# MotorControllerV2.net
KiCad netlist of a schematic drawn in EAGLE
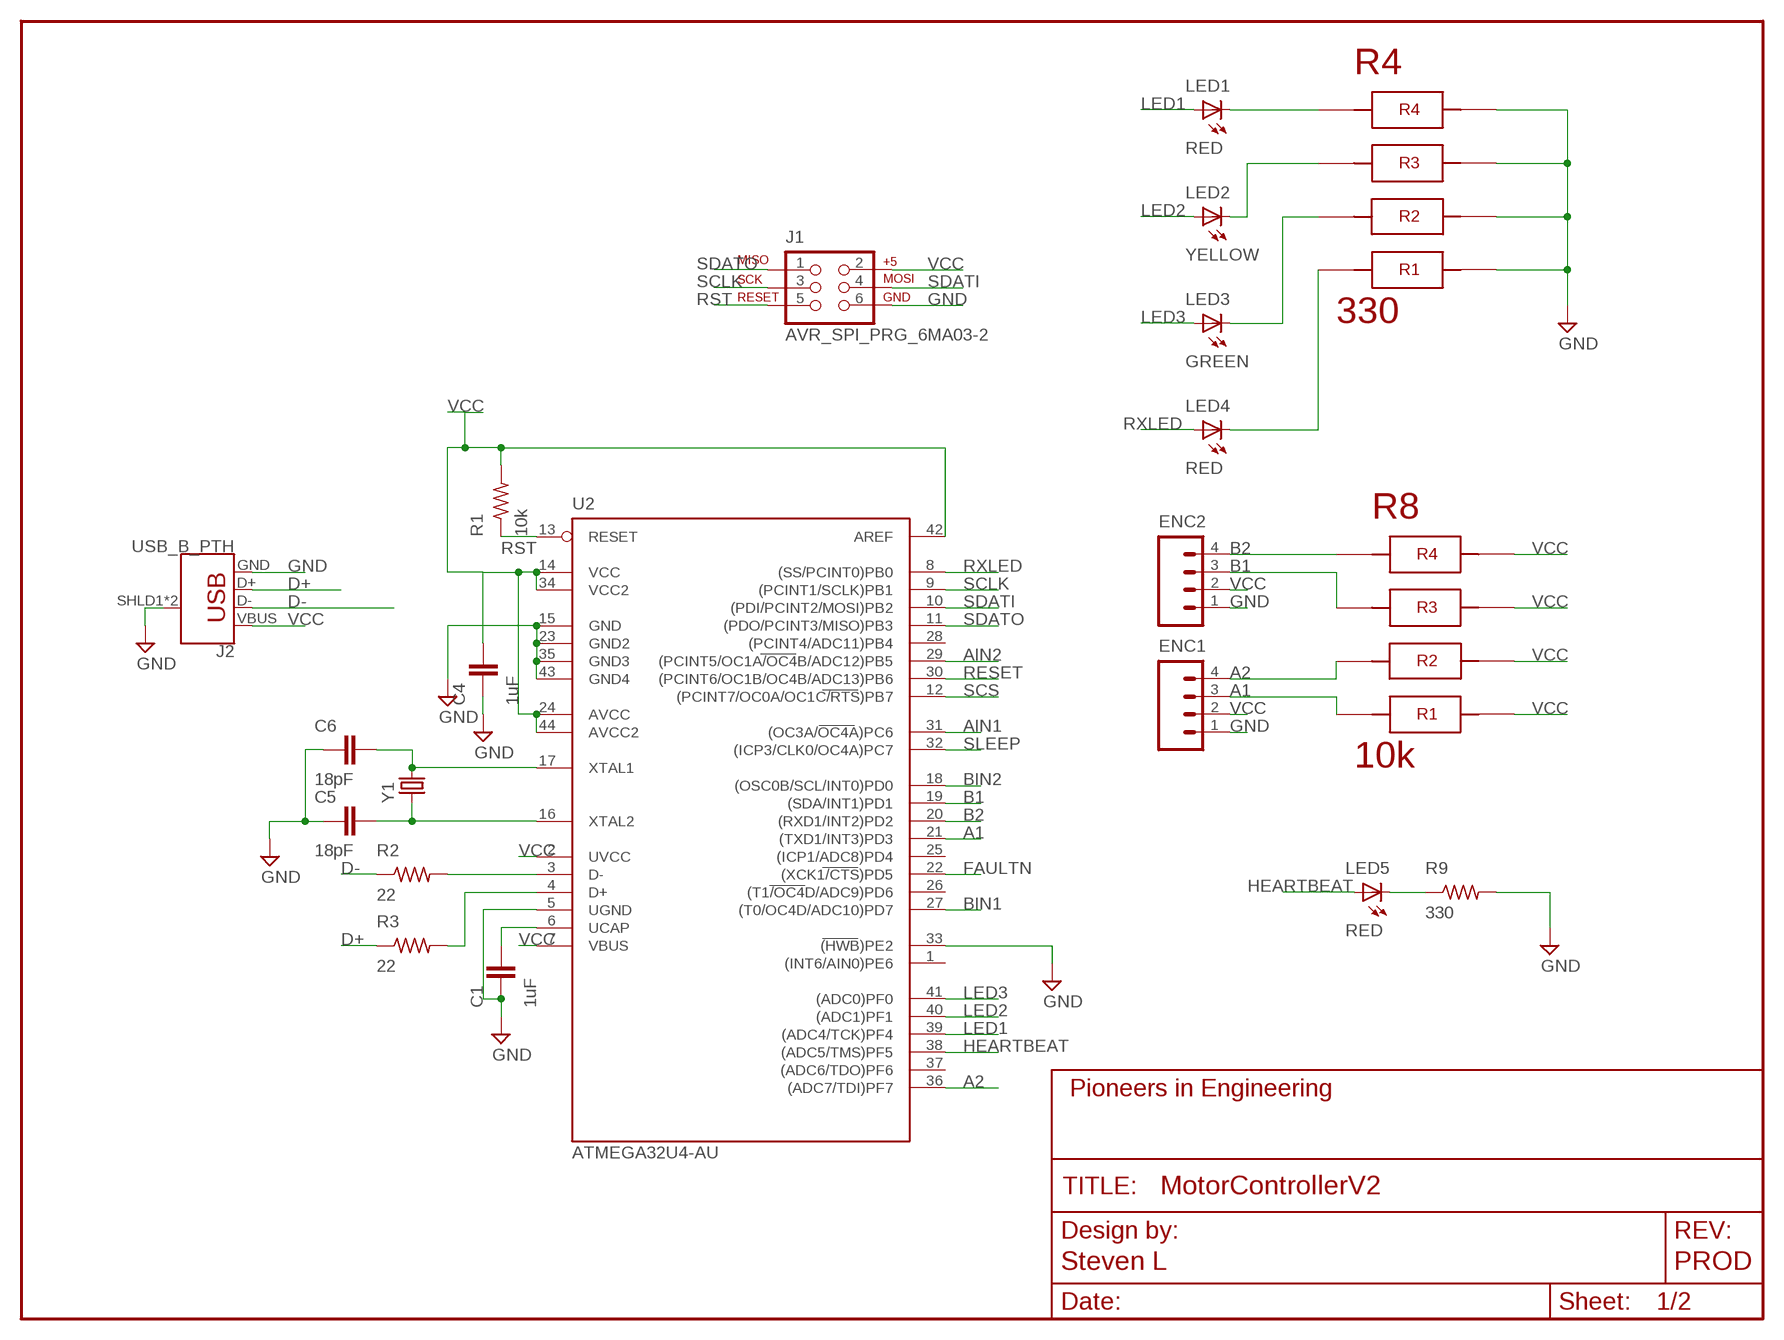
[diagram p0: schematic, sheet 1]
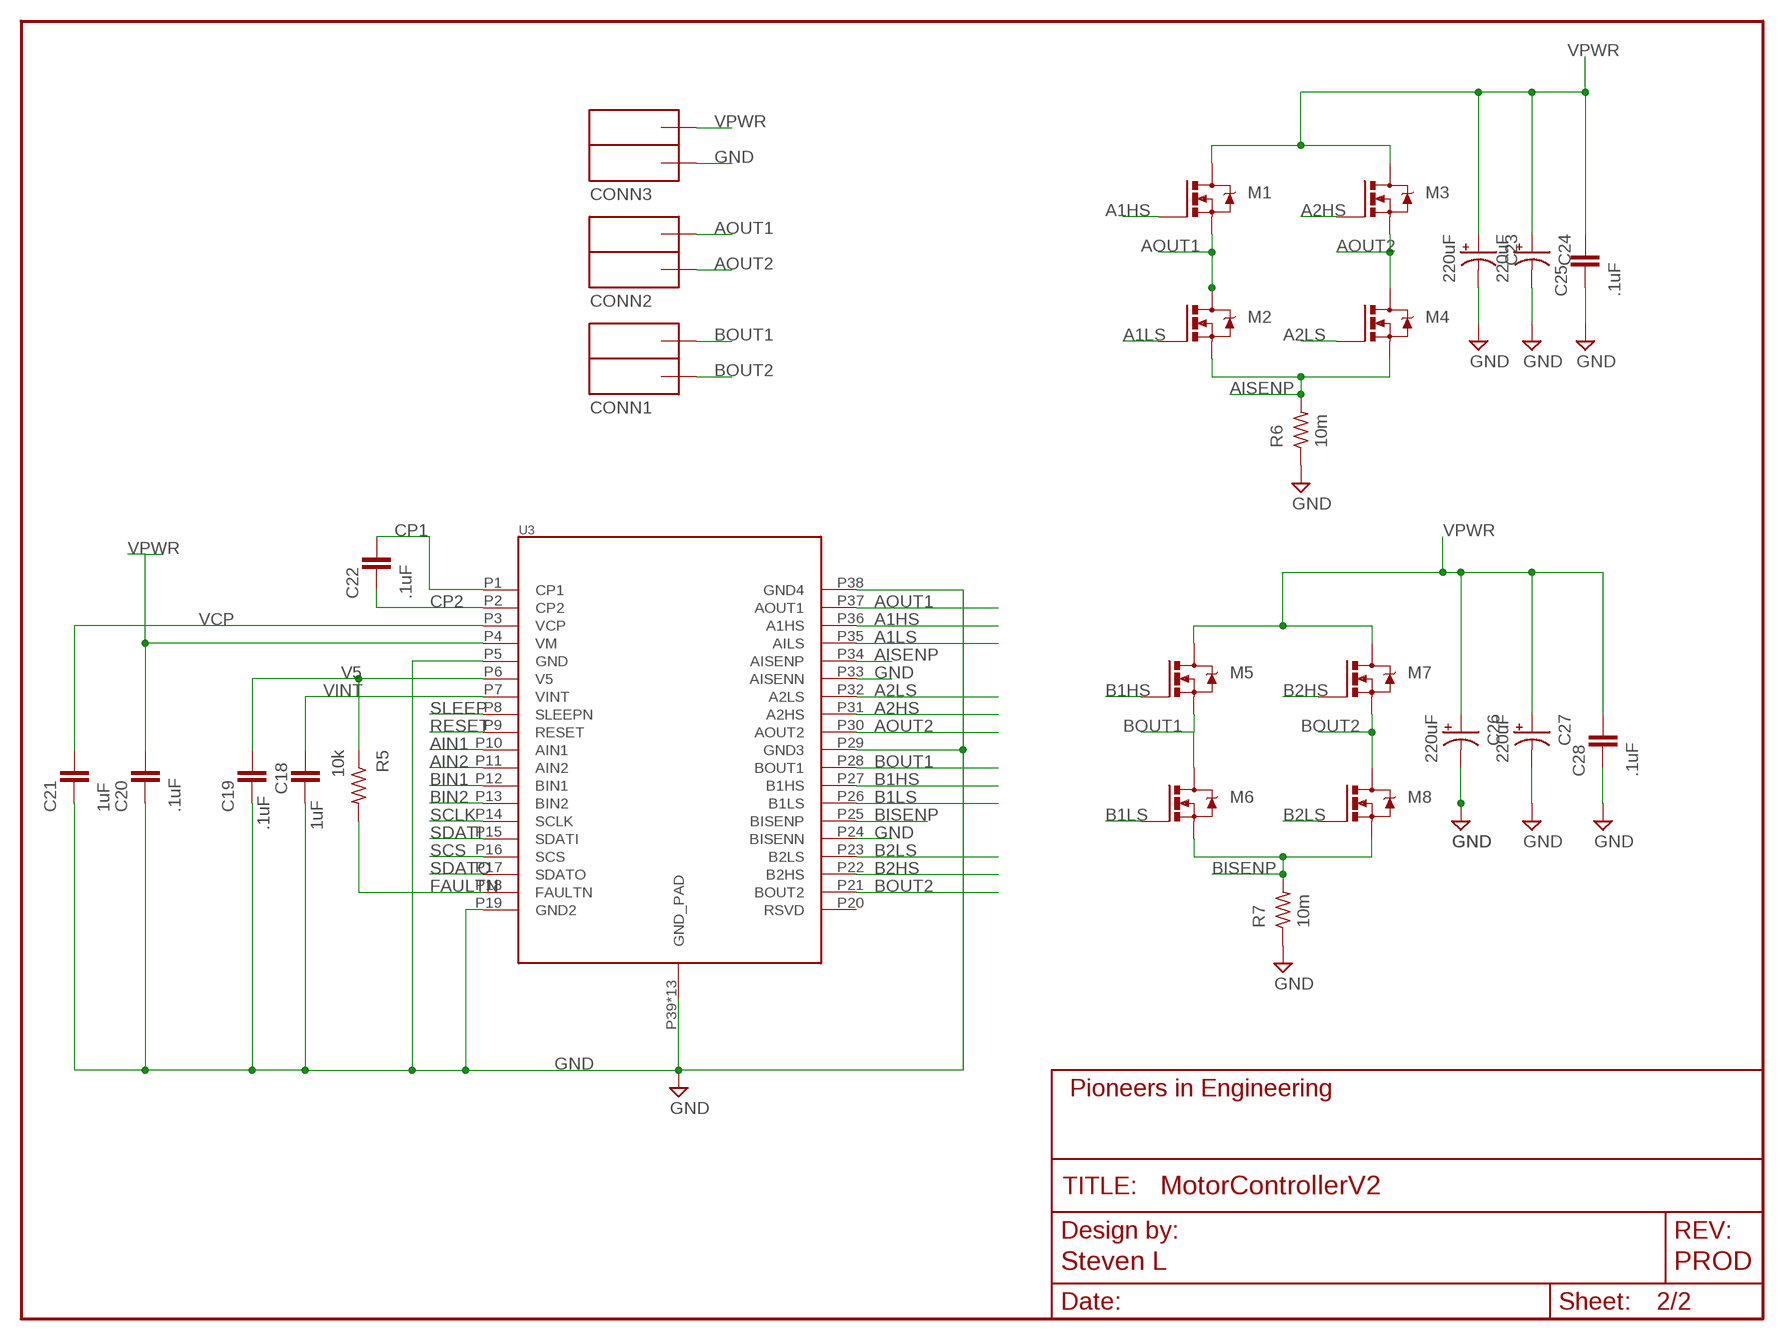
[diagram p1: schematic, sheet 2]

(export (version "E")
  (design (tool "Eeschema 10.0.6"))
  (components
    (comp (ref "C1")
      (value "1uF")
      (footprint "eagle-import:0603-CAP")
      (libsource (lib "eagle-import") (part "CAP0603-CAP"))
    )
    (comp (ref "C4")
      (value "1uF")
      (footprint "eagle-import:0603-CAP")
      (libsource (lib "eagle-import") (part "CAP0603-CAP"))
    )
    (comp (ref "C5")
      (value "18pF")
      (footprint "eagle-import:0603-CAP")
      (libsource (lib "eagle-import") (part "CAP0603-CAP"))
    )
    (comp (ref "C6")
      (value "18pF")
      (footprint "eagle-import:0603-CAP")
      (libsource (lib "eagle-import") (part "CAP0603-CAP"))
    )
    (comp (ref "ENC1")
      (value "M041X04-MTA")
      (footprint "eagle-import:1X04-MTA")
      (libsource (lib "eagle-import") (part "M041X04-MTA"))
    )
    (comp (ref "ENC2")
      (value "M041X04-MTA")
      (footprint "eagle-import:1X04-MTA")
      (libsource (lib "eagle-import") (part "M041X04-MTA"))
    )
    (comp (ref "J1")
      (value "AVR_SPI_PRG_6MA03-2")
      (footprint "eagle-import:MA03-2")
      (libsource (lib "eagle-import") (part "AVR_SPI_PRG_6MA03-2"))
    )
    (comp (ref "J2")
      (value "USB_B_PTH")
      (footprint "eagle-import:USB-B-PTH")
      (libsource (lib "eagle-import") (part "USB_B_PTH"))
    )
    (comp (ref "LED1")
      (value "RED")
      (footprint "eagle-import:LED-1206")
      (libsource (lib "eagle-import") (part "LED1206"))
    )
    (comp (ref "LED2")
      (value "YELLOW")
      (footprint "eagle-import:LED-1206")
      (libsource (lib "eagle-import") (part "LED1206"))
    )
    (comp (ref "LED3")
      (value "GREEN")
      (footprint "eagle-import:LED-1206")
      (libsource (lib "eagle-import") (part "LED1206"))
    )
    (comp (ref "LED4")
      (value "RED")
      (footprint "eagle-import:LED-1206")
      (libsource (lib "eagle-import") (part "LED1206"))
    )
    (comp (ref "LED5")
      (value "RED")
      (footprint "eagle-import:LED-1206")
      (libsource (lib "eagle-import") (part "LED1206"))
    )
    (comp (ref "R1")
      (value "10k")
      (footprint "eagle-import:R0603")
      (fields (field (name "MANUFACTURER") "Rohm Semiconductor"))
      (libsource (lib "eagle-import") (part "R-US_R0603"))
    )
    (comp (ref "R2")
      (value "22")
      (footprint "eagle-import:R0603")
      (fields (field (name "MANUFACTURER") "Rohm Semiconductor"))
      (libsource (lib "eagle-import") (part "R-US_R0603"))
    )
    (comp (ref "R3")
      (value "22")
      (footprint "eagle-import:R0603")
      (fields (field (name "MANUFACTURER") "Rohm Semiconductor"))
      (libsource (lib "eagle-import") (part "R-US_R0603"))
    )
    (comp (ref "R4")
      (value "330")
      (footprint "eagle-import:4X-0603")
      (libsource (lib "eagle-import") (part "4X-0603"))
    )
    (comp (ref "R8")
      (value "10k")
      (footprint "eagle-import:4X-0603")
      (libsource (lib "eagle-import") (part "4X-0603"))
    )
    (comp (ref "R9")
      (value "330")
      (footprint "eagle-import:R0603")
      (fields (field (name "MANUFACTURER") "Rohm Semiconductor"))
      (libsource (lib "eagle-import") (part "R-US_R0603"))
    )
    (comp (ref "U2")
      (value "ATMEGA32U4-AU")
      (footprint "eagle-import:TQFP44")
      (libsource (lib "eagle-import") (part "ATMEGA32U4-AU"))
    )
    (comp (ref "Y1")
      (value "CRYSTAL10.5X4.8")
      (footprint "eagle-import:CRYSTAL-SMD-10.5X4.8-2PIN")
      (libsource (lib "eagle-import") (part "CRYSTAL10.5X4.8"))
    )
    (comp (ref "C18")
      (value "1uF")
      (footprint "eagle-import:0603-CAP")
      (libsource (lib "eagle-import") (part "CAP0603-CAP"))
    )
    (comp (ref "C19")
      (value ".1uF")
      (footprint "eagle-import:0603-CAP")
      (libsource (lib "eagle-import") (part "CAP0603-CAP"))
    )
    (comp (ref "C20")
      (value ".1uF")
      (footprint "eagle-import:0603-CAP")
      (libsource (lib "eagle-import") (part "CAP0603-CAP"))
    )
    (comp (ref "C21")
      (value "1uF")
      (footprint "eagle-import:0603-CAP")
      (libsource (lib "eagle-import") (part "CAP0603-CAP"))
    )
    (comp (ref "C22")
      (value ".1uF")
      (footprint "eagle-import:0603-CAP")
      (libsource (lib "eagle-import") (part "CAP0603-CAP"))
    )
    (comp (ref "C23")
      (value "220uF")
      (footprint "eagle-import:NIPPON_F80")
      (libsource (lib "eagle-import") (part "CAP_POLF80"))
    )
    (comp (ref "C24")
      (value "220uF")
      (footprint "eagle-import:NIPPON_F80")
      (libsource (lib "eagle-import") (part "CAP_POLF80"))
    )
    (comp (ref "C25")
      (value ".1uF")
      (footprint "eagle-import:0603-CAP")
      (libsource (lib "eagle-import") (part "CAP0603-CAP"))
    )
    (comp (ref "C26")
      (value "220uF")
      (footprint "eagle-import:NIPPON_F80")
      (libsource (lib "eagle-import") (part "CAP_POLF80"))
    )
    (comp (ref "C27")
      (value "220uF")
      (footprint "eagle-import:NIPPON_F80")
      (libsource (lib "eagle-import") (part "CAP_POLF80"))
    )
    (comp (ref "C28")
      (value ".1uF")
      (footprint "eagle-import:0603-CAP")
      (libsource (lib "eagle-import") (part "CAP0603-CAP"))
    )
    (comp (ref "CONN1")
      (value "ANDERSONVERTICAL")
      (footprint "eagle-import:ANDERSON_VERTICAL")
      (libsource (lib "eagle-import") (part "ANDERSONVERTICAL"))
    )
    (comp (ref "CONN2")
      (value "ANDERSONVERTICAL")
      (footprint "eagle-import:ANDERSON_VERTICAL")
      (libsource (lib "eagle-import") (part "ANDERSONVERTICAL"))
    )
    (comp (ref "CONN3")
      (value "ANDERSONVERTICAL")
      (footprint "eagle-import:ANDERSON_VERTICAL")
      (libsource (lib "eagle-import") (part "ANDERSONVERTICAL"))
    )
    (comp (ref "M1")
      (value "NMOS_CSD17579Q3A")
      (footprint "eagle-import:DNH0008A")
      (fields (field (name "PART_NO") "CSD17579Q3A"))
      (libsource (lib "eagle-import") (part "NMOS_CSD17579Q3A"))
    )
    (comp (ref "M2")
      (value "NMOS_CSD17579Q3A")
      (footprint "eagle-import:DNH0008A")
      (fields (field (name "PART_NO") "CSD17579Q3A"))
      (libsource (lib "eagle-import") (part "NMOS_CSD17579Q3A"))
    )
    (comp (ref "M3")
      (value "NMOS_CSD17579Q3A")
      (footprint "eagle-import:DNH0008A")
      (fields (field (name "PART_NO") "CSD17579Q3A"))
      (libsource (lib "eagle-import") (part "NMOS_CSD17579Q3A"))
    )
    (comp (ref "M4")
      (value "NMOS_CSD17579Q3A")
      (footprint "eagle-import:DNH0008A")
      (fields (field (name "PART_NO") "CSD17579Q3A"))
      (libsource (lib "eagle-import") (part "NMOS_CSD17579Q3A"))
    )
    (comp (ref "M5")
      (value "NMOS_CSD17579Q3A")
      (footprint "eagle-import:DNH0008A")
      (fields (field (name "PART_NO") "CSD17579Q3A"))
      (libsource (lib "eagle-import") (part "NMOS_CSD17579Q3A"))
    )
    (comp (ref "M6")
      (value "NMOS_CSD17579Q3A")
      (footprint "eagle-import:DNH0008A")
      (fields (field (name "PART_NO") "CSD17579Q3A"))
      (libsource (lib "eagle-import") (part "NMOS_CSD17579Q3A"))
    )
    (comp (ref "M7")
      (value "NMOS_CSD17579Q3A")
      (footprint "eagle-import:DNH0008A")
      (fields (field (name "PART_NO") "CSD17579Q3A"))
      (libsource (lib "eagle-import") (part "NMOS_CSD17579Q3A"))
    )
    (comp (ref "M8")
      (value "NMOS_CSD17579Q3A")
      (footprint "eagle-import:DNH0008A")
      (fields (field (name "PART_NO") "CSD17579Q3A"))
      (libsource (lib "eagle-import") (part "NMOS_CSD17579Q3A"))
    )
    (comp (ref "R5")
      (value "10k")
      (footprint "eagle-import:R0603")
      (fields (field (name "MANUFACTURER") "Rohm Semiconductor"))
      (libsource (lib "eagle-import") (part "R-US_R0603"))
    )
    (comp (ref "R6")
      (value "10m")
      (footprint "eagle-import:R2512")
      (libsource (lib "eagle-import") (part "R-US_R2512"))
    )
    (comp (ref "R7")
      (value "10m")
      (footprint "eagle-import:R2512")
      (libsource (lib "eagle-import") (part "R-US_R2512"))
    )
    (comp (ref "U3")
      (value "DRV8704")
      (footprint "eagle-import:HTSSOP(38)")
      (libsource (lib "eagle-import") (part "DRV8704"))
    )
  )
  (nets
    (net (code "1") (name "A1") (class "Default")
      (node (ref "ENC1") (pin "3") (pinfunction "3_3") (pintype "passive"))
      (node (ref "R8") (pin "8") (pinfunction "8_8") (pintype "bidirectional"))
      (node (ref "U2") (pin "21") (pinfunction "(TXD1/INT3)PD3_21") (pintype "bidirectional"))
    )
    (net (code "2") (name "A1HS") (class "Default")
      (node (ref "M1") (pin "4") (pinfunction "G_4") (pintype "passive"))
      (node (ref "U3") (pin "P36") (pinfunction "A1HS_P36") (pintype "bidirectional"))
    )
    (net (code "3") (name "A1LS") (class "Default")
      (node (ref "M2") (pin "4") (pinfunction "G_4") (pintype "passive"))
      (node (ref "U3") (pin "P35") (pinfunction "AILS_P35") (pintype "bidirectional"))
    )
    (net (code "4") (name "A2") (class "Default")
      (node (ref "ENC1") (pin "4") (pinfunction "4_4") (pintype "passive"))
      (node (ref "R8") (pin "7") (pinfunction "7_7") (pintype "bidirectional"))
      (node (ref "U2") (pin "36") (pinfunction "(ADC7/TDI)PF7_36") (pintype "bidirectional"))
    )
    (net (code "5") (name "A2HS") (class "Default")
      (node (ref "M3") (pin "4") (pinfunction "G_4") (pintype "passive"))
      (node (ref "U3") (pin "P31") (pinfunction "A2HS_P31") (pintype "bidirectional"))
    )
    (net (code "6") (name "A2LS") (class "Default")
      (node (ref "M4") (pin "4") (pinfunction "G_4") (pintype "passive"))
      (node (ref "U3") (pin "P32") (pinfunction "A2LS_P32") (pintype "bidirectional"))
    )
    (net (code "7") (name "AIN1") (class "Default")
      (node (ref "U2") (pin "31") (pinfunction "(OC3A/OC4A)PC6_31") (pintype "bidirectional"))
      (node (ref "U3") (pin "P10") (pinfunction "AIN1_P10") (pintype "bidirectional"))
    )
    (net (code "8") (name "AIN2") (class "Default")
      (node (ref "U2") (pin "29") (pinfunction "(PCINT5/OC1A/OC4B/ADC12)PB5_29") (pintype "bidirectional"))
      (node (ref "U3") (pin "P11") (pinfunction "AIN2_P11") (pintype "bidirectional"))
    )
    (net (code "9") (name "AISENP") (class "Default")
      (node (ref "M2") (pin "1") (pinfunction "S_1") (pintype "passive"))
      (node (ref "M2") (pin "2") (pinfunction "S_2") (pintype "passive"))
      (node (ref "M2") (pin "3") (pinfunction "S_3") (pintype "passive"))
      (node (ref "M4") (pin "1") (pinfunction "S_1") (pintype "passive"))
      (node (ref "M4") (pin "2") (pinfunction "S_2") (pintype "passive"))
      (node (ref "M4") (pin "3") (pinfunction "S_3") (pintype "passive"))
      (node (ref "R6") (pin "2") (pinfunction "2_2") (pintype "passive"))
      (node (ref "U3") (pin "P34") (pinfunction "AISENP_P34") (pintype "bidirectional"))
    )
    (net (code "10") (name "AOUT1") (class "Default")
      (node (ref "CONN2") (pin "PIN1") (pinfunction "OUTB_PIN1") (pintype "bidirectional"))
      (node (ref "M1") (pin "1") (pinfunction "S_1") (pintype "passive"))
      (node (ref "M1") (pin "2") (pinfunction "S_2") (pintype "passive"))
      (node (ref "M1") (pin "3") (pinfunction "S_3") (pintype "passive"))
      (node (ref "M2") (pin "5") (pinfunction "D_5") (pintype "passive"))
      (node (ref "M2") (pin "6") (pinfunction "D_6") (pintype "passive"))
      (node (ref "M2") (pin "7") (pinfunction "D_7") (pintype "passive"))
      (node (ref "M2") (pin "8") (pinfunction "D_8") (pintype "passive"))
      (node (ref "M2") (pin "9") (pinfunction "D_9") (pintype "passive"))
      (node (ref "U3") (pin "P37") (pinfunction "AOUT1_P37") (pintype "bidirectional"))
    )
    (net (code "11") (name "AOUT2") (class "Default")
      (node (ref "CONN2") (pin "PIN2") (pinfunction "OUTA_PIN2") (pintype "bidirectional"))
      (node (ref "M3") (pin "1") (pinfunction "S_1") (pintype "passive"))
      (node (ref "M3") (pin "2") (pinfunction "S_2") (pintype "passive"))
      (node (ref "M3") (pin "3") (pinfunction "S_3") (pintype "passive"))
      (node (ref "M4") (pin "5") (pinfunction "D_5") (pintype "passive"))
      (node (ref "M4") (pin "6") (pinfunction "D_6") (pintype "passive"))
      (node (ref "M4") (pin "7") (pinfunction "D_7") (pintype "passive"))
      (node (ref "M4") (pin "8") (pinfunction "D_8") (pintype "passive"))
      (node (ref "M4") (pin "9") (pinfunction "D_9") (pintype "passive"))
      (node (ref "U3") (pin "P30") (pinfunction "AOUT2_P30") (pintype "bidirectional"))
    )
    (net (code "12") (name "B1") (class "Default")
      (node (ref "ENC2") (pin "3") (pinfunction "3_3") (pintype "passive"))
      (node (ref "R8") (pin "6") (pinfunction "6_6") (pintype "bidirectional"))
      (node (ref "U2") (pin "19") (pinfunction "(SDA/INT1)PD1_19") (pintype "bidirectional"))
    )
    (net (code "13") (name "B1HS") (class "Default")
      (node (ref "M5") (pin "4") (pinfunction "G_4") (pintype "passive"))
      (node (ref "U3") (pin "P27") (pinfunction "B1HS_P27") (pintype "bidirectional"))
    )
    (net (code "14") (name "B1LS") (class "Default")
      (node (ref "M6") (pin "4") (pinfunction "G_4") (pintype "passive"))
      (node (ref "U3") (pin "P26") (pinfunction "B1LS_P26") (pintype "bidirectional"))
    )
    (net (code "15") (name "B2") (class "Default")
      (node (ref "ENC2") (pin "4") (pinfunction "4_4") (pintype "passive"))
      (node (ref "R8") (pin "5") (pinfunction "5_5") (pintype "bidirectional"))
      (node (ref "U2") (pin "20") (pinfunction "(RXD1/INT2)PD2_20") (pintype "bidirectional"))
    )
    (net (code "16") (name "B2HS") (class "Default")
      (node (ref "M7") (pin "4") (pinfunction "G_4") (pintype "passive"))
      (node (ref "U3") (pin "P22") (pinfunction "B2HS_P22") (pintype "bidirectional"))
    )
    (net (code "17") (name "B2LS") (class "Default")
      (node (ref "M8") (pin "4") (pinfunction "G_4") (pintype "passive"))
      (node (ref "U3") (pin "P23") (pinfunction "B2LS_P23") (pintype "bidirectional"))
    )
    (net (code "18") (name "BIN1") (class "Default")
      (node (ref "U2") (pin "27") (pinfunction "(T0/OC4D/ADC10)PD7_27") (pintype "bidirectional"))
      (node (ref "U3") (pin "P12") (pinfunction "BIN1_P12") (pintype "bidirectional"))
    )
    (net (code "19") (name "BIN2") (class "Default")
      (node (ref "U2") (pin "18") (pinfunction "(OSC0B/SCL/INT0)PD0_18") (pintype "bidirectional"))
      (node (ref "U3") (pin "P13") (pinfunction "BIN2_P13") (pintype "bidirectional"))
    )
    (net (code "20") (name "BISENP") (class "Default")
      (node (ref "M6") (pin "1") (pinfunction "S_1") (pintype "passive"))
      (node (ref "M6") (pin "2") (pinfunction "S_2") (pintype "passive"))
      (node (ref "M6") (pin "3") (pinfunction "S_3") (pintype "passive"))
      (node (ref "M8") (pin "1") (pinfunction "S_1") (pintype "passive"))
      (node (ref "M8") (pin "2") (pinfunction "S_2") (pintype "passive"))
      (node (ref "M8") (pin "3") (pinfunction "S_3") (pintype "passive"))
      (node (ref "R7") (pin "2") (pinfunction "2_2") (pintype "passive"))
      (node (ref "U3") (pin "P25") (pinfunction "BISENP_P25") (pintype "bidirectional"))
    )
    (net (code "21") (name "BOUT1") (class "Default")
      (node (ref "CONN1") (pin "PIN1") (pinfunction "OUTB_PIN1") (pintype "bidirectional"))
      (node (ref "M5") (pin "1") (pinfunction "S_1") (pintype "passive"))
      (node (ref "M5") (pin "2") (pinfunction "S_2") (pintype "passive"))
      (node (ref "M5") (pin "3") (pinfunction "S_3") (pintype "passive"))
      (node (ref "M6") (pin "5") (pinfunction "D_5") (pintype "passive"))
      (node (ref "M6") (pin "6") (pinfunction "D_6") (pintype "passive"))
      (node (ref "M6") (pin "7") (pinfunction "D_7") (pintype "passive"))
      (node (ref "M6") (pin "8") (pinfunction "D_8") (pintype "passive"))
      (node (ref "M6") (pin "9") (pinfunction "D_9") (pintype "passive"))
      (node (ref "U3") (pin "P28") (pinfunction "BOUT1_P28") (pintype "bidirectional"))
    )
    (net (code "22") (name "BOUT2") (class "Default")
      (node (ref "CONN1") (pin "PIN2") (pinfunction "OUTA_PIN2") (pintype "bidirectional"))
      (node (ref "M7") (pin "1") (pinfunction "S_1") (pintype "passive"))
      (node (ref "M7") (pin "2") (pinfunction "S_2") (pintype "passive"))
      (node (ref "M7") (pin "3") (pinfunction "S_3") (pintype "passive"))
      (node (ref "M8") (pin "5") (pinfunction "D_5") (pintype "passive"))
      (node (ref "M8") (pin "6") (pinfunction "D_6") (pintype "passive"))
      (node (ref "M8") (pin "7") (pinfunction "D_7") (pintype "passive"))
      (node (ref "M8") (pin "8") (pinfunction "D_8") (pintype "passive"))
      (node (ref "M8") (pin "9") (pinfunction "D_9") (pintype "passive"))
      (node (ref "U3") (pin "P21") (pinfunction "BOUT2_P21") (pintype "bidirectional"))
    )
    (net (code "23") (name "CP1") (class "Default")
      (node (ref "C22") (pin "2") (pinfunction "2_2") (pintype "passive"))
      (node (ref "U3") (pin "P1") (pinfunction "CP1_P1") (pintype "bidirectional"))
    )
    (net (code "24") (name "CP2") (class "Default")
      (node (ref "C22") (pin "1") (pinfunction "1_1") (pintype "passive"))
      (node (ref "U3") (pin "P2") (pinfunction "CP2_P2") (pintype "bidirectional"))
    )
    (net (code "25") (name "D+") (class "Default")
      (node (ref "J2") (pin "D+") (pinfunction "D+_D+") (pintype "bidirectional"))
      (node (ref "R3") (pin "1") (pinfunction "1_1") (pintype "passive"))
    )
    (net (code "26") (name "D-") (class "Default")
      (node (ref "J2") (pin "D-") (pinfunction "D-_D-") (pintype "bidirectional"))
      (node (ref "R2") (pin "1") (pinfunction "1_1") (pintype "passive"))
    )
    (net (code "27") (name "FAULTN") (class "Default")
      (node (ref "R5") (pin "2") (pinfunction "2_2") (pintype "passive"))
      (node (ref "U2") (pin "22") (pinfunction "(XCK1/CTS)PD5_22") (pintype "bidirectional"))
      (node (ref "U3") (pin "P18") (pinfunction "FAULTN_P18") (pintype "bidirectional"))
    )
    (net (code "28") (name "GND") (class "Default")
      (node (ref "C1") (pin "1") (pinfunction "1_1") (pintype "passive"))
      (node (ref "C18") (pin "1") (pinfunction "1_1") (pintype "passive"))
      (node (ref "C19") (pin "1") (pinfunction "1_1") (pintype "passive"))
      (node (ref "C20") (pin "1") (pinfunction "1_1") (pintype "passive"))
      (node (ref "C21") (pin "1") (pinfunction "1_1") (pintype "passive"))
      (node (ref "C23") (pin "-") (pinfunction "-_-") (pintype "passive"))
      (node (ref "C24") (pin "-") (pinfunction "-_-") (pintype "passive"))
      (node (ref "C25") (pin "1") (pinfunction "1_1") (pintype "passive"))
      (node (ref "C26") (pin "-") (pinfunction "-_-") (pintype "passive"))
      (node (ref "C27") (pin "-") (pinfunction "-_-") (pintype "passive"))
      (node (ref "C28") (pin "1") (pinfunction "1_1") (pintype "passive"))
      (node (ref "C4") (pin "1") (pinfunction "1_1") (pintype "passive"))
      (node (ref "C5") (pin "1") (pinfunction "1_1") (pintype "passive"))
      (node (ref "C6") (pin "1") (pinfunction "1_1") (pintype "passive"))
      (node (ref "CONN3") (pin "PIN2") (pinfunction "OUTA_PIN2") (pintype "bidirectional"))
      (node (ref "ENC1") (pin "1") (pinfunction "1_1") (pintype "passive"))
      (node (ref "ENC2") (pin "1") (pinfunction "1_1") (pintype "passive"))
      (node (ref "J1") (pin "6") (pinfunction "6_6") (pintype "passive"))
      (node (ref "J2") (pin "GND") (pinfunction "GND_GND") (pintype "power_in"))
      (node (ref "J2") (pin "SHLD1") (pinfunction "SHIELD_SHLD1") (pintype "bidirectional"))
      (node (ref "J2") (pin "SHLD2") (pinfunction "SHIELD_SHLD2") (pintype "bidirectional"))
      (node (ref "R4") (pin "1") (pinfunction "1_1") (pintype "bidirectional"))
      (node (ref "R4") (pin "2") (pinfunction "2_2") (pintype "bidirectional"))
      (node (ref "R4") (pin "3") (pinfunction "3_3") (pintype "bidirectional"))
      (node (ref "R4") (pin "4") (pinfunction "4_4") (pintype "bidirectional"))
      (node (ref "R6") (pin "1") (pinfunction "1_1") (pintype "passive"))
      (node (ref "R7") (pin "1") (pinfunction "1_1") (pintype "passive"))
      (node (ref "R9") (pin "2") (pinfunction "2_2") (pintype "passive"))
      (node (ref "U2") (pin "15") (pinfunction "GND_15") (pintype "bidirectional"))
      (node (ref "U2") (pin "23") (pinfunction "GND2_23") (pintype "bidirectional"))
      (node (ref "U2") (pin "33") (pinfunction "(HWB)PE2_33") (pintype "bidirectional"))
      (node (ref "U2") (pin "35") (pinfunction "GND3_35") (pintype "bidirectional"))
      (node (ref "U2") (pin "43") (pinfunction "GND4_43") (pintype "bidirectional"))
      (node (ref "U2") (pin "5") (pinfunction "UGND_5") (pintype "bidirectional"))
      (node (ref "U3") (pin "P19") (pinfunction "GND2_P19") (pintype "bidirectional"))
      (node (ref "U3") (pin "P24") (pinfunction "BISENN_P24") (pintype "bidirectional"))
      (node (ref "U3") (pin "P29") (pinfunction "GND3_P29") (pintype "bidirectional"))
      (node (ref "U3") (pin "P33") (pinfunction "AISENN_P33") (pintype "bidirectional"))
      (node (ref "U3") (pin "P38") (pinfunction "GND4_P38") (pintype "bidirectional"))
      (node (ref "U3") (pin "P39") (pinfunction "GND_PAD_P39") (pintype "bidirectional"))
      (node (ref "U3") (pin "P40") (pinfunction "GND_PAD_P40") (pintype "bidirectional"))
      (node (ref "U3") (pin "P41") (pinfunction "GND_PAD_P41") (pintype "bidirectional"))
      (node (ref "U3") (pin "P42") (pinfunction "GND_PAD_P42") (pintype "bidirectional"))
      (node (ref "U3") (pin "P43") (pinfunction "GND_PAD_P43") (pintype "bidirectional"))
      (node (ref "U3") (pin "P44") (pinfunction "GND_PAD_P44") (pintype "bidirectional"))
      (node (ref "U3") (pin "P45") (pinfunction "GND_PAD_P45") (pintype "bidirectional"))
      (node (ref "U3") (pin "P46") (pinfunction "GND_PAD_P46") (pintype "bidirectional"))
      (node (ref "U3") (pin "P47") (pinfunction "GND_PAD_P47") (pintype "bidirectional"))
      (node (ref "U3") (pin "P48") (pinfunction "GND_PAD_P48") (pintype "bidirectional"))
      (node (ref "U3") (pin "P49") (pinfunction "GND_PAD_P49") (pintype "bidirectional"))
      (node (ref "U3") (pin "P5") (pinfunction "GND_P5") (pintype "bidirectional"))
      (node (ref "U3") (pin "P50") (pinfunction "GND_PAD_P50") (pintype "bidirectional"))
      (node (ref "U3") (pin "P51") (pinfunction "GND_PAD_P51") (pintype "bidirectional"))
    )
    (net (code "29") (name "HEARTBEAT") (class "Default")
      (node (ref "LED5") (pin "A") (pinfunction "A_A") (pintype "passive"))
      (node (ref "U2") (pin "38") (pinfunction "(ADC5/TMS)PF5_38") (pintype "bidirectional"))
    )
    (net (code "30") (name "LED1") (class "Default")
      (node (ref "LED1") (pin "A") (pinfunction "A_A") (pintype "passive"))
      (node (ref "U2") (pin "39") (pinfunction "(ADC4/TCK)PF4_39") (pintype "bidirectional"))
    )
    (net (code "31") (name "LED2") (class "Default")
      (node (ref "LED2") (pin "A") (pinfunction "A_A") (pintype "passive"))
      (node (ref "U2") (pin "40") (pinfunction "(ADC1)PF1_40") (pintype "bidirectional"))
    )
    (net (code "32") (name "LED3") (class "Default")
      (node (ref "LED3") (pin "A") (pinfunction "A_A") (pintype "passive"))
      (node (ref "U2") (pin "41") (pinfunction "(ADC0)PF0_41") (pintype "bidirectional"))
    )
    (net (code "33") (name "Net-(LED1-PadC)") (class "Default")
      (node (ref "LED1") (pin "C") (pinfunction "C_C") (pintype "passive"))
      (node (ref "R4") (pin "5") (pinfunction "5_5") (pintype "bidirectional"))
    )
    (net (code "34") (name "Net-(LED2-PadC)") (class "Default")
      (node (ref "LED2") (pin "C") (pinfunction "C_C") (pintype "passive"))
      (node (ref "R4") (pin "6") (pinfunction "6_6") (pintype "bidirectional"))
    )
    (net (code "35") (name "Net-(LED3-PadC)") (class "Default")
      (node (ref "LED3") (pin "C") (pinfunction "C_C") (pintype "passive"))
      (node (ref "R4") (pin "7") (pinfunction "7_7") (pintype "bidirectional"))
    )
    (net (code "36") (name "Net-(LED4-PadC)") (class "Default")
      (node (ref "LED4") (pin "C") (pinfunction "C_C") (pintype "passive"))
      (node (ref "R4") (pin "8") (pinfunction "8_8") (pintype "bidirectional"))
    )
    (net (code "37") (name "Net-(LED5-PadC)") (class "Default")
      (node (ref "LED5") (pin "C") (pinfunction "C_C") (pintype "passive"))
      (node (ref "R9") (pin "1") (pinfunction "1_1") (pintype "passive"))
    )
    (net (code "38") (name "Net-(U2-D+)") (class "Default")
      (node (ref "R3") (pin "2") (pinfunction "2_2") (pintype "passive"))
      (node (ref "U2") (pin "4") (pinfunction "D+_4") (pintype "bidirectional"))
    )
    (net (code "39") (name "Net-(U2-D-)") (class "Default")
      (node (ref "R2") (pin "2") (pinfunction "2_2") (pintype "passive"))
      (node (ref "U2") (pin "3") (pinfunction "D-_3") (pintype "bidirectional"))
    )
    (net (code "40") (name "Net-(U2-UCAP)") (class "Default")
      (node (ref "C1") (pin "2") (pinfunction "2_2") (pintype "passive"))
      (node (ref "U2") (pin "6") (pinfunction "UCAP_6") (pintype "bidirectional"))
    )
    (net (code "41") (name "Net-(U2-XTAL1)") (class "Default")
      (node (ref "C6") (pin "2") (pinfunction "2_2") (pintype "passive"))
      (node (ref "U2") (pin "17") (pinfunction "XTAL1_17") (pintype "bidirectional"))
      (node (ref "Y1") (pin "P$2") (pinfunction "2_P$2") (pintype "passive"))
    )
    (net (code "42") (name "Net-(U2-XTAL2)") (class "Default")
      (node (ref "C5") (pin "2") (pinfunction "2_2") (pintype "passive"))
      (node (ref "U2") (pin "16") (pinfunction "XTAL2_16") (pintype "bidirectional"))
      (node (ref "Y1") (pin "P$1") (pinfunction "1_P$1") (pintype "passive"))
    )
    (net (code "43") (name "RESET") (class "Default")
      (node (ref "U2") (pin "30") (pinfunction "(PCINT6/OC1B/OC4B/ADC13)PB6_30") (pintype "bidirectional"))
      (node (ref "U3") (pin "P9") (pinfunction "RESET_P9") (pintype "bidirectional"))
    )
    (net (code "44") (name "RST") (class "Default")
      (node (ref "J1") (pin "5") (pinfunction "5_5") (pintype "passive"))
      (node (ref "R1") (pin "1") (pinfunction "1_1") (pintype "passive"))
      (node (ref "U2") (pin "13") (pinfunction "RESET_13") (pintype "bidirectional"))
    )
    (net (code "45") (name "RXLED") (class "Default")
      (node (ref "LED4") (pin "A") (pinfunction "A_A") (pintype "passive"))
      (node (ref "U2") (pin "8") (pinfunction "(SS/PCINT0)PB0_8") (pintype "bidirectional"))
    )
    (net (code "46") (name "SCLK") (class "Default")
      (node (ref "J1") (pin "3") (pinfunction "3_3") (pintype "passive"))
      (node (ref "U2") (pin "9") (pinfunction "(PCINT1/SCLK)PB1_9") (pintype "bidirectional"))
      (node (ref "U3") (pin "P14") (pinfunction "SCLK_P14") (pintype "bidirectional"))
    )
    (net (code "47") (name "SCS") (class "Default")
      (node (ref "U2") (pin "12") (pinfunction "(PCINT7/OC0A/OC1C/RTS)PB7_12") (pintype "bidirectional"))
      (node (ref "U3") (pin "P16") (pinfunction "SCS_P16") (pintype "bidirectional"))
    )
    (net (code "48") (name "SDATI") (class "Default")
      (node (ref "J1") (pin "4") (pinfunction "4_4") (pintype "passive"))
      (node (ref "U2") (pin "10") (pinfunction "(PDI/PCINT2/MOSI)PB2_10") (pintype "bidirectional"))
      (node (ref "U3") (pin "P15") (pinfunction "SDATI_P15") (pintype "bidirectional"))
    )
    (net (code "49") (name "SDATO") (class "Default")
      (node (ref "J1") (pin "1") (pinfunction "1_1") (pintype "passive"))
      (node (ref "U2") (pin "11") (pinfunction "(PDO/PCINT3/MISO)PB3_11") (pintype "bidirectional"))
      (node (ref "U3") (pin "P17") (pinfunction "SDATO_P17") (pintype "bidirectional"))
    )
    (net (code "50") (name "SLEEP") (class "Default")
      (node (ref "U2") (pin "32") (pinfunction "(ICP3/CLK0/OC4A)PC7_32") (pintype "bidirectional"))
      (node (ref "U3") (pin "P8") (pinfunction "SLEEPN_P8") (pintype "bidirectional"))
    )
    (net (code "51") (name "V5") (class "Default")
      (node (ref "C19") (pin "2") (pinfunction "2_2") (pintype "passive"))
      (node (ref "R5") (pin "1") (pinfunction "1_1") (pintype "passive"))
      (node (ref "U3") (pin "P6") (pinfunction "V5_P6") (pintype "bidirectional"))
    )
    (net (code "52") (name "VCC") (class "Default")
      (node (ref "C4") (pin "2") (pinfunction "2_2") (pintype "passive"))
      (node (ref "ENC1") (pin "2") (pinfunction "2_2") (pintype "passive"))
      (node (ref "ENC2") (pin "2") (pinfunction "2_2") (pintype "passive"))
      (node (ref "J1") (pin "2") (pinfunction "2_2") (pintype "passive"))
      (node (ref "J2") (pin "VBUS") (pinfunction "VBUS_VBUS") (pintype "power_in"))
      (node (ref "R1") (pin "2") (pinfunction "2_2") (pintype "passive"))
      (node (ref "R8") (pin "1") (pinfunction "1_1") (pintype "bidirectional"))
      (node (ref "R8") (pin "2") (pinfunction "2_2") (pintype "bidirectional"))
      (node (ref "R8") (pin "3") (pinfunction "3_3") (pintype "bidirectional"))
      (node (ref "R8") (pin "4") (pinfunction "4_4") (pintype "bidirectional"))
      (node (ref "U2") (pin "14") (pinfunction "VCC_14") (pintype "bidirectional"))
      (node (ref "U2") (pin "2") (pinfunction "UVCC_2") (pintype "bidirectional"))
      (node (ref "U2") (pin "24") (pinfunction "AVCC_24") (pintype "bidirectional"))
      (node (ref "U2") (pin "34") (pinfunction "VCC2_34") (pintype "bidirectional"))
      (node (ref "U2") (pin "42") (pinfunction "AREF_42") (pintype "bidirectional"))
      (node (ref "U2") (pin "44") (pinfunction "AVCC2_44") (pintype "bidirectional"))
      (node (ref "U2") (pin "7") (pinfunction "VBUS_7") (pintype "bidirectional"))
    )
    (net (code "53") (name "VCP") (class "Default")
      (node (ref "C21") (pin "2") (pinfunction "2_2") (pintype "passive"))
      (node (ref "U3") (pin "P3") (pinfunction "VCP_P3") (pintype "bidirectional"))
    )
    (net (code "54") (name "VINT") (class "Default")
      (node (ref "C18") (pin "2") (pinfunction "2_2") (pintype "passive"))
      (node (ref "U3") (pin "P7") (pinfunction "VINT_P7") (pintype "bidirectional"))
    )
    (net (code "55") (name "VPWR") (class "Default")
      (node (ref "C20") (pin "2") (pinfunction "2_2") (pintype "passive"))
      (node (ref "C23") (pin "+") (pinfunction "+_+") (pintype "passive"))
      (node (ref "C24") (pin "+") (pinfunction "+_+") (pintype "passive"))
      (node (ref "C25") (pin "2") (pinfunction "2_2") (pintype "passive"))
      (node (ref "C26") (pin "+") (pinfunction "+_+") (pintype "passive"))
      (node (ref "C27") (pin "+") (pinfunction "+_+") (pintype "passive"))
      (node (ref "C28") (pin "2") (pinfunction "2_2") (pintype "passive"))
      (node (ref "CONN3") (pin "PIN1") (pinfunction "OUTB_PIN1") (pintype "bidirectional"))
      (node (ref "M1") (pin "5") (pinfunction "D_5") (pintype "passive"))
      (node (ref "M1") (pin "6") (pinfunction "D_6") (pintype "passive"))
      (node (ref "M1") (pin "7") (pinfunction "D_7") (pintype "passive"))
      (node (ref "M1") (pin "8") (pinfunction "D_8") (pintype "passive"))
      (node (ref "M1") (pin "9") (pinfunction "D_9") (pintype "passive"))
      (node (ref "M3") (pin "5") (pinfunction "D_5") (pintype "passive"))
      (node (ref "M3") (pin "6") (pinfunction "D_6") (pintype "passive"))
      (node (ref "M3") (pin "7") (pinfunction "D_7") (pintype "passive"))
      (node (ref "M3") (pin "8") (pinfunction "D_8") (pintype "passive"))
      (node (ref "M3") (pin "9") (pinfunction "D_9") (pintype "passive"))
      (node (ref "M5") (pin "5") (pinfunction "D_5") (pintype "passive"))
      (node (ref "M5") (pin "6") (pinfunction "D_6") (pintype "passive"))
      (node (ref "M5") (pin "7") (pinfunction "D_7") (pintype "passive"))
      (node (ref "M5") (pin "8") (pinfunction "D_8") (pintype "passive"))
      (node (ref "M5") (pin "9") (pinfunction "D_9") (pintype "passive"))
      (node (ref "M7") (pin "5") (pinfunction "D_5") (pintype "passive"))
      (node (ref "M7") (pin "6") (pinfunction "D_6") (pintype "passive"))
      (node (ref "M7") (pin "7") (pinfunction "D_7") (pintype "passive"))
      (node (ref "M7") (pin "8") (pinfunction "D_8") (pintype "passive"))
      (node (ref "M7") (pin "9") (pinfunction "D_9") (pintype "passive"))
      (node (ref "U3") (pin "P4") (pinfunction "VM_P4") (pintype "bidirectional"))
    )
    (net (code "56") (name "unconnected-(U2-(ADC6{slash}TDO)PF6-Pad37)") (class "Default")
      (node (ref "U2") (pin "37") (pinfunction "(ADC6/TDO)PF6_37") (pintype "bidirectional"))
    )
    (net (code "57") (name "unconnected-(U2-(ICP1{slash}ADC8)PD4-Pad25)") (class "Default")
      (node (ref "U2") (pin "25") (pinfunction "(ICP1/ADC8)PD4_25") (pintype "bidirectional"))
    )
    (net (code "58") (name "unconnected-(U2-(INT6{slash}AIN0)PE6-Pad1)") (class "Default")
      (node (ref "U2") (pin "1") (pinfunction "(INT6/AIN0)PE6_1") (pintype "bidirectional"))
    )
    (net (code "59") (name "unconnected-(U2-(PCINT4{slash}ADC11)PB4-Pad28)") (class "Default")
      (node (ref "U2") (pin "28") (pinfunction "(PCINT4/ADC11)PB4_28") (pintype "bidirectional"))
    )
    (net (code "60") (name "unconnected-(U2-(T1{slash}OC4D{slash}ADC9)PD6-Pad26)") (class "Default")
      (node (ref "U2") (pin "26") (pinfunction "(T1/OC4D/ADC9)PD6_26") (pintype "bidirectional"))
    )
    (net (code "61") (name "unconnected-(U3-RSVD-PadP20)") (class "Default")
      (node (ref "U3") (pin "P20") (pinfunction "RSVD_P20") (pintype "bidirectional"))
    )
  )
)
